# E2_Transistor_Blank.net
KiCad netlist of a schematic drawn in EAGLE
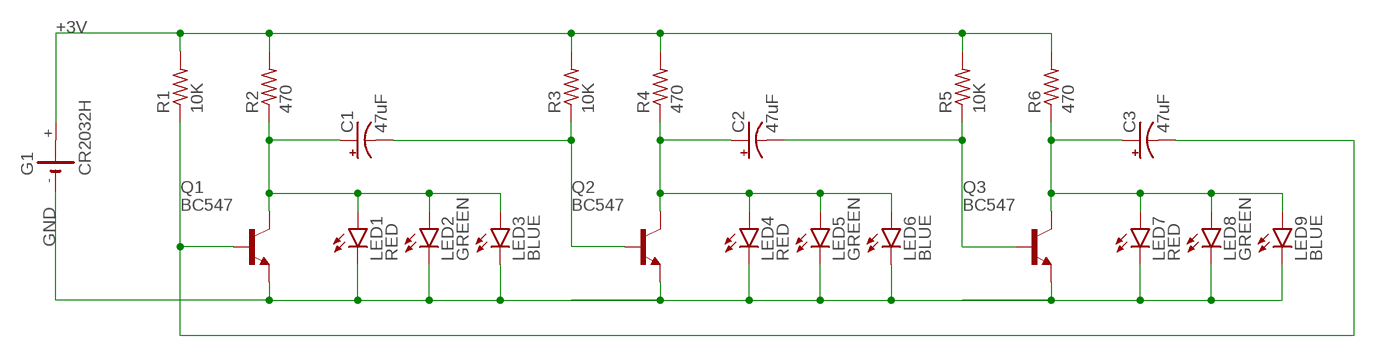
[diagram p0: schematic, sheet 1]

(export (version "E")
  (design (tool "Eeschema 10.0.6"))
  (components
    (comp (ref "C1")
      (value "47uF")
      (footprint "eagle-import:E1,8-4")
      (libsource (lib "eagle-import") (part "CPOL-USE1.8-4"))
    )
    (comp (ref "C2")
      (value "47uF")
      (footprint "eagle-import:E1,8-4")
      (libsource (lib "eagle-import") (part "CPOL-USE1.8-4"))
    )
    (comp (ref "C3")
      (value "47uF")
      (footprint "eagle-import:E1,8-4")
      (libsource (lib "eagle-import") (part "CPOL-USE1.8-4"))
    )
    (comp (ref "G1")
      (value "CR2032H")
      (footprint "eagle-import:CR2032H")
      (libsource (lib "eagle-import") (part "CR2032H"))
    )
    (comp (ref "LED1")
      (value "RED")
      (footprint "eagle-import:LED5MM")
      (libsource (lib "eagle-import") (part "LED5MM"))
    )
    (comp (ref "LED2")
      (value "GREEN")
      (footprint "eagle-import:LED5MM")
      (libsource (lib "eagle-import") (part "LED5MM"))
    )
    (comp (ref "LED3")
      (value "BLUE")
      (footprint "eagle-import:LED5MM")
      (libsource (lib "eagle-import") (part "LED5MM"))
    )
    (comp (ref "LED4")
      (value "RED")
      (footprint "eagle-import:LED5MM")
      (libsource (lib "eagle-import") (part "LED5MM"))
    )
    (comp (ref "LED5")
      (value "GREEN")
      (footprint "eagle-import:LED5MM")
      (libsource (lib "eagle-import") (part "LED5MM"))
    )
    (comp (ref "LED6")
      (value "BLUE")
      (footprint "eagle-import:LED5MM")
      (libsource (lib "eagle-import") (part "LED5MM"))
    )
    (comp (ref "LED7")
      (value "RED")
      (footprint "eagle-import:LED5MM")
      (libsource (lib "eagle-import") (part "LED5MM"))
    )
    (comp (ref "LED8")
      (value "GREEN")
      (footprint "eagle-import:LED5MM")
      (libsource (lib "eagle-import") (part "LED5MM"))
    )
    (comp (ref "LED9")
      (value "BLUE")
      (footprint "eagle-import:LED5MM")
      (libsource (lib "eagle-import") (part "LED5MM"))
    )
    (comp (ref "Q1")
      (value "BC547")
      (footprint "eagle-import:TO92")
      (libsource (lib "eagle-import") (part "BC547"))
    )
    (comp (ref "Q2")
      (value "BC547")
      (footprint "eagle-import:TO92")
      (libsource (lib "eagle-import") (part "BC547"))
    )
    (comp (ref "Q3")
      (value "BC547")
      (footprint "eagle-import:TO92")
      (libsource (lib "eagle-import") (part "BC547"))
    )
    (comp (ref "R1")
      (value "10K")
      (footprint "eagle-import:0309_12")
      (libsource (lib "eagle-import") (part "R-US_0309/12"))
    )
    (comp (ref "R2")
      (value "470")
      (footprint "eagle-import:0309_12")
      (libsource (lib "eagle-import") (part "R-US_0309/12"))
    )
    (comp (ref "R3")
      (value "10K")
      (footprint "eagle-import:0309_12")
      (libsource (lib "eagle-import") (part "R-US_0309/12"))
    )
    (comp (ref "R4")
      (value "470")
      (footprint "eagle-import:0309_12")
      (libsource (lib "eagle-import") (part "R-US_0309/12"))
    )
    (comp (ref "R5")
      (value "10K")
      (footprint "eagle-import:0309_12")
      (libsource (lib "eagle-import") (part "R-US_0309/12"))
    )
    (comp (ref "R6")
      (value "470")
      (footprint "eagle-import:0309_12")
      (libsource (lib "eagle-import") (part "R-US_0309/12"))
    )
  )
  (nets
    (net (code "1") (name "/+3V") (class "Default")
      (node (ref "G1") (pin "+") (pinfunction "+_+") (pintype "passive"))
      (node (ref "R1") (pin "2") (pinfunction "2_2") (pintype "passive"))
      (node (ref "R2") (pin "2") (pinfunction "2_2") (pintype "passive"))
      (node (ref "R3") (pin "2") (pinfunction "2_2") (pintype "passive"))
      (node (ref "R4") (pin "2") (pinfunction "2_2") (pintype "passive"))
      (node (ref "R5") (pin "2") (pinfunction "2_2") (pintype "passive"))
      (node (ref "R6") (pin "2") (pinfunction "2_2") (pintype "passive"))
    )
    (net (code "2") (name "/GND") (class "Default")
      (node (ref "G1") (pin "-") (pinfunction "-_-") (pintype "passive"))
      (node (ref "LED1") (pin "K") (pinfunction "C_K") (pintype "passive"))
      (node (ref "LED2") (pin "K") (pinfunction "C_K") (pintype "passive"))
      (node (ref "LED3") (pin "K") (pinfunction "C_K") (pintype "passive"))
      (node (ref "LED4") (pin "K") (pinfunction "C_K") (pintype "passive"))
      (node (ref "LED5") (pin "K") (pinfunction "C_K") (pintype "passive"))
      (node (ref "LED6") (pin "K") (pinfunction "C_K") (pintype "passive"))
      (node (ref "LED7") (pin "K") (pinfunction "C_K") (pintype "passive"))
      (node (ref "LED8") (pin "K") (pinfunction "C_K") (pintype "passive"))
      (node (ref "LED9") (pin "K") (pinfunction "C_K") (pintype "passive"))
      (node (ref "Q1") (pin "1") (pinfunction "E_1") (pintype "passive"))
      (node (ref "Q2") (pin "1") (pinfunction "E_1") (pintype "passive"))
      (node (ref "Q3") (pin "1") (pinfunction "E_1") (pintype "passive"))
    )
    (net (code "3") (name "Net-(Q1-B)") (class "Default")
      (node (ref "C3") (pin "-") (pinfunction "-_-") (pintype "passive"))
      (node (ref "Q1") (pin "2") (pinfunction "B_2") (pintype "passive"))
      (node (ref "R1") (pin "1") (pinfunction "1_1") (pintype "passive"))
    )
    (net (code "4") (name "Net-(Q1-C)") (class "Default")
      (node (ref "C1") (pin "+") (pinfunction "+_+") (pintype "passive"))
      (node (ref "LED1") (pin "A") (pinfunction "A_A") (pintype "passive"))
      (node (ref "LED2") (pin "A") (pinfunction "A_A") (pintype "passive"))
      (node (ref "LED3") (pin "A") (pinfunction "A_A") (pintype "passive"))
      (node (ref "Q1") (pin "3") (pinfunction "C_3") (pintype "passive"))
      (node (ref "R2") (pin "1") (pinfunction "1_1") (pintype "passive"))
    )
    (net (code "5") (name "Net-(Q2-B)") (class "Default")
      (node (ref "C1") (pin "-") (pinfunction "-_-") (pintype "passive"))
      (node (ref "Q2") (pin "2") (pinfunction "B_2") (pintype "passive"))
      (node (ref "R3") (pin "1") (pinfunction "1_1") (pintype "passive"))
    )
    (net (code "6") (name "Net-(Q2-C)") (class "Default")
      (node (ref "C2") (pin "+") (pinfunction "+_+") (pintype "passive"))
      (node (ref "LED4") (pin "A") (pinfunction "A_A") (pintype "passive"))
      (node (ref "LED5") (pin "A") (pinfunction "A_A") (pintype "passive"))
      (node (ref "LED6") (pin "A") (pinfunction "A_A") (pintype "passive"))
      (node (ref "Q2") (pin "3") (pinfunction "C_3") (pintype "passive"))
      (node (ref "R4") (pin "1") (pinfunction "1_1") (pintype "passive"))
    )
    (net (code "7") (name "Net-(Q3-B)") (class "Default")
      (node (ref "C2") (pin "-") (pinfunction "-_-") (pintype "passive"))
      (node (ref "Q3") (pin "2") (pinfunction "B_2") (pintype "passive"))
      (node (ref "R5") (pin "1") (pinfunction "1_1") (pintype "passive"))
    )
    (net (code "8") (name "Net-(Q3-C)") (class "Default")
      (node (ref "C3") (pin "+") (pinfunction "+_+") (pintype "passive"))
      (node (ref "LED7") (pin "A") (pinfunction "A_A") (pintype "passive"))
      (node (ref "LED8") (pin "A") (pinfunction "A_A") (pintype "passive"))
      (node (ref "LED9") (pin "A") (pinfunction "A_A") (pintype "passive"))
      (node (ref "Q3") (pin "3") (pinfunction "C_3") (pintype "passive"))
      (node (ref "R6") (pin "1") (pinfunction "1_1") (pintype "passive"))
    )
    (net (code "9") (name "unconnected-(G1-+-Pad+@1)") (class "Default")
      (node (ref "G1") (pin "+@1") (pinfunction "+_+@1") (pintype "passive"))
    )
  )
)
